# 07_-_PERIPHERALS_B.net
KiCad netlist of a schematic drawn in Altium Designer
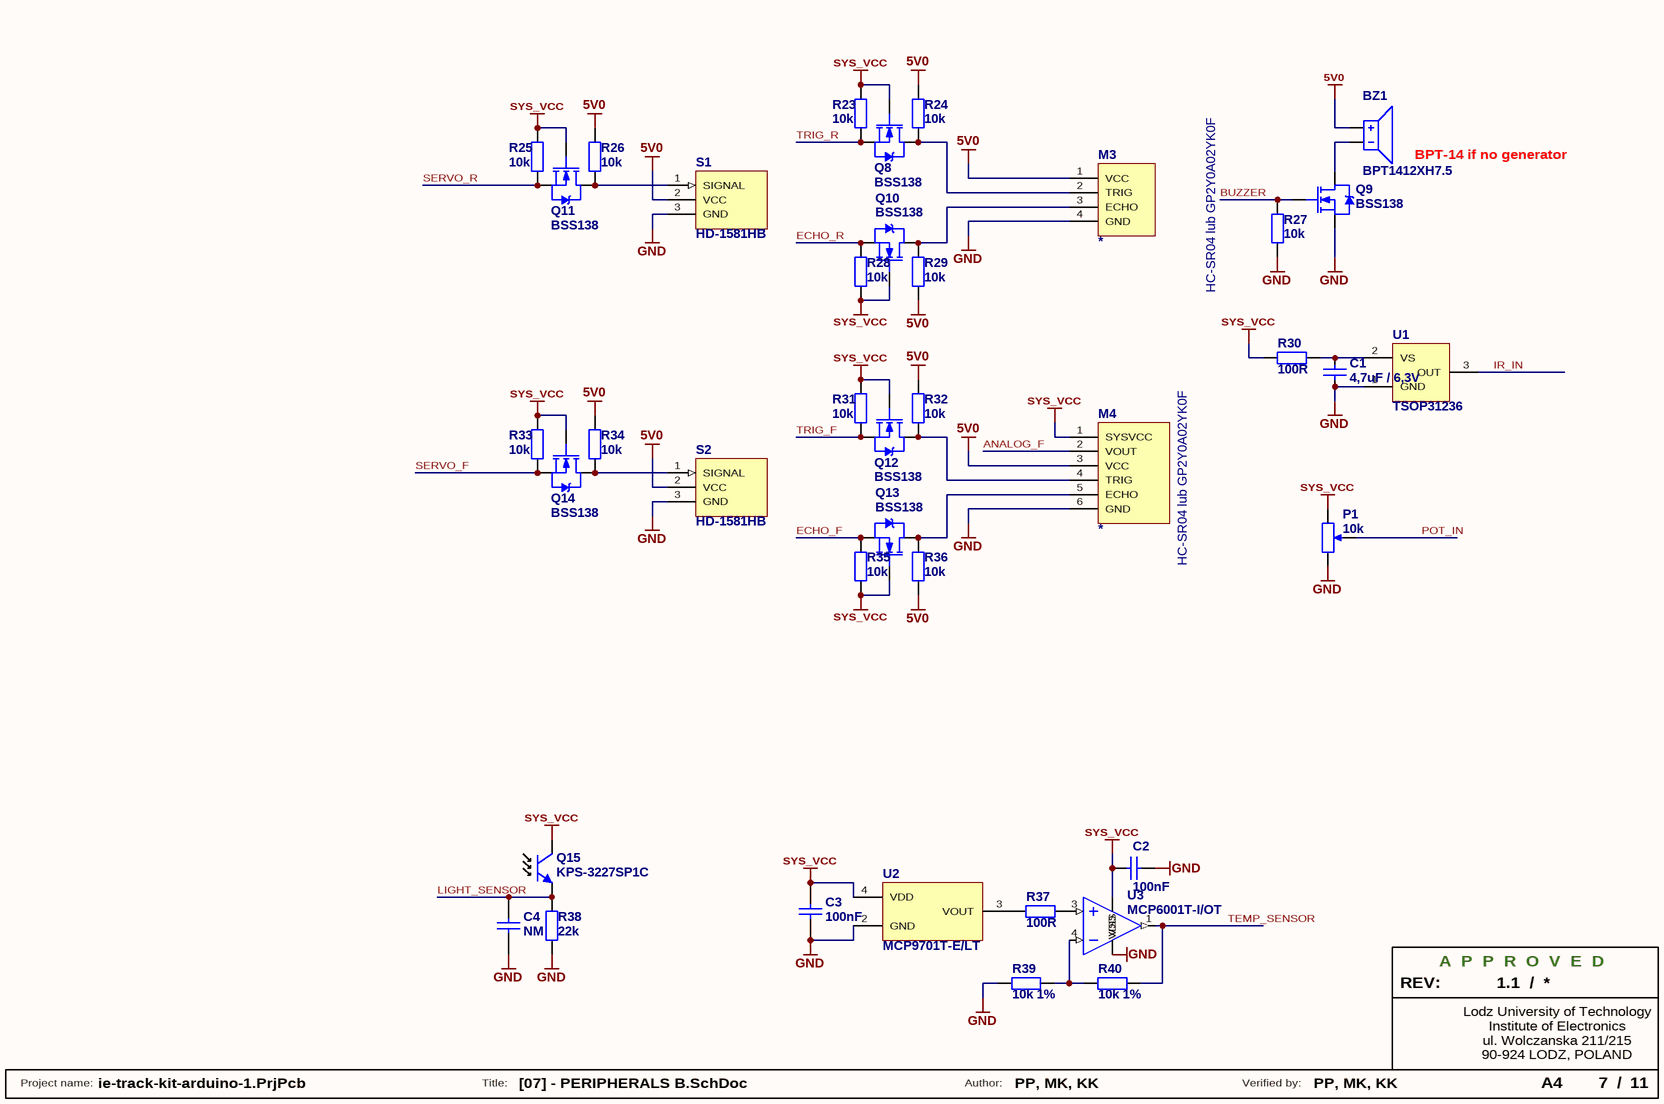
[diagram p0: [07] - PERIPHERALS B.SchDoc]

(export (version "E")
  (design (tool "Eeschema 10.0.6"))
  (components
    (comp (ref "BZ1")
      (value "BPT1412XH7.5")
      (footprint "BUZ-13,8-7,6")
      (description "Piezoelectric Sound Transducer: 5Vp-p; 4kHz; O:14mm; with generator")
      (fields (field (name "PUBLISHER") "Altium Limited"))
      (libsource (lib "sounders") (part "BPT1412XH7.5"))
    )
    (comp (ref "C1")
      (value "4,7uF / 6,3V")
      (footprint "C0805")
      (description "Capacitor")
      (libsource (lib "") (part "Cap_1"))
    )
    (comp (ref "C2")
      (value "100nF")
      (footprint "C0805")
      (description "Capacitor")
      (libsource (lib "") (part "Cap_2"))
    )
    (comp (ref "C3")
      (value "100nF")
      (footprint "C0805")
      (description "Capacitor")
      (libsource (lib "capacitors") (part "Cap"))
    )
    (comp (ref "C4")
      (value "NM")
      (footprint "C0805")
      (description "Capacitor")
      (libsource (lib "capacitors") (part "Cap"))
    )
    (comp (ref "M3") (value "*") (footprint "HC-SR04") (libsource (lib "other_modules") (part "HC-SR04")))
    (comp (ref "M4")
      (value "*")
      (footprint "HC-SR04_UNIV")
      (libsource (lib "other_modules") (part "HC-SR04_UNIVERSAL"))
    )
    (comp (ref "P1")
      (value "10k")
      (footprint "RK09K113004U")
      (description "RK09K113004U")
      (libsource (lib "resistors") (part "RK09K113004U"))
    )
    (comp (ref "Q8")
      (value "BSS138")
      (footprint "SOT-23")
      (description "N-Channel Enhancement Mode Vertical DMOS FET")
      (fields (field (name "PUBLISHER") "Altium Limited"))
      (libsource (lib "transistors_other") (part "BSS138"))
    )
    (comp (ref "Q9")
      (value "BSS138")
      (footprint "SOT-23")
      (description "N-Channel Enhancement Mode Vertical DMOS FET")
      (fields (field (name "PUBLISHER") "Altium Limited"))
      (libsource (lib "transistors_other") (part "BSS138"))
    )
    (comp (ref "Q10")
      (value "BSS138")
      (footprint "SOT-23")
      (description "N-Channel Enhancement Mode Vertical DMOS FET")
      (fields (field (name "PUBLISHER") "Altium Limited"))
      (libsource (lib "transistors_other") (part "BSS138"))
    )
    (comp (ref "Q11")
      (value "BSS138")
      (footprint "SOT-23")
      (description "N-Channel Enhancement Mode Vertical DMOS FET")
      (fields (field (name "PUBLISHER") "Altium Limited"))
      (libsource (lib "transistors_other") (part "BSS138"))
    )
    (comp (ref "Q12")
      (value "BSS138")
      (footprint "SOT-23")
      (description "N-Channel Enhancement Mode Vertical DMOS FET")
      (fields (field (name "PUBLISHER") "Altium Limited"))
      (libsource (lib "transistors_other") (part "BSS138"))
    )
    (comp (ref "Q13")
      (value "BSS138")
      (footprint "SOT-23")
      (description "N-Channel Enhancement Mode Vertical DMOS FET")
      (fields (field (name "PUBLISHER") "Altium Limited"))
      (libsource (lib "transistors_other") (part "BSS138"))
    )
    (comp (ref "Q14")
      (value "BSS138")
      (footprint "SOT-23")
      (description "N-Channel Enhancement Mode Vertical DMOS FET")
      (fields (field (name "PUBLISHER") "Altium Limited"))
      (libsource (lib "transistors_other") (part "BSS138"))
    )
    (comp (ref "Q15")
      (value "KPS-3227SP1C")
      (footprint "KPS-3227")
      (description "Photo Transistor 60V 0,1mA 580nm (TME KPS-3227SP1C)")
      (libsource (lib "photoelements") (part "KPS-3227SP1C"))
    )
    (comp (ref "R23")
      (value "10k")
      (footprint "R0805")
      (description "Resistor")
      (libsource (lib "resistors") (part "Res"))
    )
    (comp (ref "R24")
      (value "10k")
      (footprint "R0805")
      (description "Resistor")
      (libsource (lib "resistors") (part "Res"))
    )
    (comp (ref "R25")
      (value "10k")
      (footprint "R0805")
      (description "Resistor")
      (libsource (lib "resistors") (part "Res"))
    )
    (comp (ref "R26")
      (value "10k")
      (footprint "R0805")
      (description "Resistor")
      (libsource (lib "resistors") (part "Res"))
    )
    (comp (ref "R27")
      (value "10k")
      (footprint "R0805")
      (description "Resistor")
      (libsource (lib "") (part "Res_3"))
    )
    (comp (ref "R28")
      (value "10k")
      (footprint "R0805")
      (description "Resistor")
      (libsource (lib "") (part "Res_2"))
    )
    (comp (ref "R29")
      (value "10k")
      (footprint "R0805")
      (description "Resistor")
      (libsource (lib "") (part "Res_2"))
    )
    (comp (ref "R30")
      (value "100R")
      (footprint "R0805")
      (description "Resistor")
      (libsource (lib "") (part "Res_4"))
    )
    (comp (ref "R31")
      (value "10k")
      (footprint "R0805")
      (description "Resistor")
      (libsource (lib "resistors") (part "Res"))
    )
    (comp (ref "R32")
      (value "10k")
      (footprint "R0805")
      (description "Resistor")
      (libsource (lib "resistors") (part "Res"))
    )
    (comp (ref "R33")
      (value "10k")
      (footprint "R0805")
      (description "Resistor")
      (libsource (lib "resistors") (part "Res"))
    )
    (comp (ref "R34")
      (value "10k")
      (footprint "R0805")
      (description "Resistor")
      (libsource (lib "resistors") (part "Res"))
    )
    (comp (ref "R35")
      (value "10k")
      (footprint "R0805")
      (description "Resistor")
      (libsource (lib "") (part "Res_2"))
    )
    (comp (ref "R36")
      (value "10k")
      (footprint "R0805")
      (description "Resistor")
      (libsource (lib "") (part "Res_2"))
    )
    (comp (ref "R37")
      (value "100R")
      (footprint "R0805")
      (description "Resistor")
      (libsource (lib "") (part "Res_1"))
    )
    (comp (ref "R38")
      (value "22k")
      (footprint "R0805")
      (description "Resistor")
      (libsource (lib "") (part "Res_3"))
    )
    (comp (ref "R39")
      (value "10k 1%")
      (footprint "R0805")
      (description "Resistor")
      (libsource (lib "") (part "Res_1"))
    )
    (comp (ref "R40")
      (value "10k 1%")
      (footprint "R0805")
      (description "Resistor")
      (libsource (lib "") (part "Res_1"))
    )
    (comp (ref "S1")
      (value "HD-1581HB")
      (footprint "HD-1581HB_VERTICAL_1")
      (description "HD-1581HB Micro Servo")
      (libsource (lib "servos") (part "HD-1581HB"))
    )
    (comp (ref "S2")
      (value "HD-1581HB")
      (footprint "HD-1581HB_VERTICAL_1")
      (description "HD-1581HB Micro Servo")
      (libsource (lib "servos") (part "HD-1581HB"))
    )
    (comp (ref "U1")
      (value "TSOP31236")
      (footprint "TSOP312(4)_H")
      (description "36kHz IR Receiver Module for Remote Control Systems")
      (libsource (lib "ir_receivers") (part "TSOP31236"))
    )
    (comp (ref "U2")
      (value "MCP9701T-E/LT")
      (footprint "SOT-323-5 (SOT-353, SC70-5)")
      (description "Low-Power Linear Active Thermistor IC")
      (libsource (lib "temperature_transducers") (part "MCP9701T-E/LT"))
    )
    (comp (ref "U3")
      (value "MCP6001T-I/OT")
      (footprint "SOT-23-5")
      (description "Rail-to-rail, 1MHz, 100uA Op Amp")
      (libsource (lib "opamps") (part "MCP6001T-I/OT"))
    )
  )
  (nets
    (net (code "1") (name "/ANALOG_F") (class "Default")
      (node (ref "M4") (pin "2") (pinfunction "VOUT_2") (pintype "power_in"))
    )
    (net (code "2") (name "/BUZZER") (class "Default")
      (node (ref "Q9") (pin "1") (pinfunction "G_1") (pintype "passive"))
      (node (ref "R27") (pin "1") (pinfunction "1_1") (pintype "passive"))
    )
    (net (code "3") (name "/ECHO_F") (class "Default")
      (node (ref "Q13") (pin "2") (pinfunction "S_2") (pintype "passive"))
      (node (ref "R35") (pin "1") (pinfunction "1_1") (pintype "passive"))
    )
    (net (code "4") (name "/ECHO_R") (class "Default")
      (node (ref "Q10") (pin "2") (pinfunction "S_2") (pintype "passive"))
      (node (ref "R28") (pin "1") (pinfunction "1_1") (pintype "passive"))
    )
    (net (code "5") (name "/IR_IN") (class "Default")
      (node (ref "U1") (pin "3") (pinfunction "OUT_3") (pintype "passive"))
    )
    (net (code "6") (name "/LIGHT_SENSOR") (class "Default")
      (node (ref "C4") (pin "2") (pinfunction "2_2") (pintype "passive"))
      (node (ref "Q15") (pin "1") (pinfunction "E_1") (pintype "passive"))
      (node (ref "R38") (pin "1") (pinfunction "1_1") (pintype "passive"))
    )
    (net (code "7") (name "/POT_IN") (class "Default")
      (node (ref "P1") (pin "2") (pinfunction "TAP_2") (pintype "passive"))
    )
    (net (code "8") (name "/SERVO_F") (class "Default")
      (node (ref "Q14") (pin "2") (pinfunction "S_2") (pintype "passive"))
      (node (ref "R33") (pin "1") (pinfunction "1_1") (pintype "passive"))
    )
    (net (code "9") (name "/SERVO_R") (class "Default")
      (node (ref "Q11") (pin "2") (pinfunction "S_2") (pintype "passive"))
      (node (ref "R25") (pin "1") (pinfunction "1_1") (pintype "passive"))
    )
    (net (code "10") (name "/TEMP_SENSOR") (class "Default")
      (node (ref "R40") (pin "1") (pinfunction "1_1") (pintype "passive"))
      (node (ref "U3") (pin "1") (pinfunction "OUT_1") (pintype "output"))
    )
    (net (code "11") (name "/TRIG_F") (class "Default")
      (node (ref "Q12") (pin "2") (pinfunction "S_2") (pintype "passive"))
      (node (ref "R31") (pin "1") (pinfunction "1_1") (pintype "passive"))
    )
    (net (code "12") (name "/TRIG_R") (class "Default")
      (node (ref "Q8") (pin "2") (pinfunction "S_2") (pintype "passive"))
      (node (ref "R23") (pin "1") (pinfunction "1_1") (pintype "passive"))
    )
    (net (code "13") (name "5V0") (class "Default")
      (node (ref "BZ1") (pin "1") (pinfunction "1_1") (pintype "passive"))
      (node (ref "M3") (pin "1") (pinfunction "VCC_1") (pintype "power_in"))
      (node (ref "M4") (pin "3") (pinfunction "VCC_3") (pintype "power_in"))
      (node (ref "R24") (pin "2") (pinfunction "2_2") (pintype "passive"))
      (node (ref "R26") (pin "2") (pinfunction "2_2") (pintype "passive"))
      (node (ref "R29") (pin "2") (pinfunction "2_2") (pintype "passive"))
      (node (ref "R32") (pin "2") (pinfunction "2_2") (pintype "passive"))
      (node (ref "R34") (pin "2") (pinfunction "2_2") (pintype "passive"))
      (node (ref "R36") (pin "2") (pinfunction "2_2") (pintype "passive"))
      (node (ref "S1") (pin "2") (pinfunction "VCC_2") (pintype "power_in"))
      (node (ref "S2") (pin "2") (pinfunction "VCC_2") (pintype "power_in"))
    )
    (net (code "14") (name "GND") (class "Default")
      (node (ref "C1") (pin "1") (pinfunction "1_1") (pintype "passive"))
      (node (ref "C2") (pin "2") (pinfunction "2_2") (pintype "passive"))
      (node (ref "C3") (pin "1") (pinfunction "1_1") (pintype "passive"))
      (node (ref "C4") (pin "1") (pinfunction "1_1") (pintype "passive"))
      (node (ref "M3") (pin "4") (pinfunction "GND_4") (pintype "power_in"))
      (node (ref "M4") (pin "6") (pinfunction "GND_6") (pintype "power_in"))
      (node (ref "P1") (pin "3") (pinfunction "BOT_3") (pintype "passive"))
      (node (ref "Q9") (pin "2") (pinfunction "S_2") (pintype "passive"))
      (node (ref "R27") (pin "2") (pinfunction "2_2") (pintype "passive"))
      (node (ref "R38") (pin "2") (pinfunction "2_2") (pintype "passive"))
      (node (ref "R39") (pin "2") (pinfunction "2_2") (pintype "passive"))
      (node (ref "S1") (pin "3") (pinfunction "GND_3") (pintype "power_in"))
      (node (ref "S2") (pin "3") (pinfunction "GND_3") (pintype "power_in"))
      (node (ref "U1") (pin "1") (pinfunction "GND_1") (pintype "passive"))
      (node (ref "U2") (pin "2") (pinfunction "GND_2") (pintype "passive"))
      (node (ref "U3") (pin "2") (pinfunction "VSS_2") (pintype "power_in"))
    )
    (net (code "15") (name "Net-(M3-ECHO)") (class "Default")
      (node (ref "M3") (pin "3") (pinfunction "ECHO_3") (pintype "power_in"))
      (node (ref "Q10") (pin "3") (pinfunction "D_3") (pintype "passive"))
      (node (ref "R29") (pin "1") (pinfunction "1_1") (pintype "passive"))
    )
    (net (code "16") (name "Net-(M3-TRIG)") (class "Default")
      (node (ref "M3") (pin "2") (pinfunction "TRIG_2") (pintype "power_in"))
      (node (ref "Q8") (pin "3") (pinfunction "D_3") (pintype "passive"))
      (node (ref "R24") (pin "1") (pinfunction "1_1") (pintype "passive"))
    )
    (net (code "17") (name "Net-(M4-ECHO)") (class "Default")
      (node (ref "M4") (pin "5") (pinfunction "ECHO_5") (pintype "power_in"))
      (node (ref "Q13") (pin "3") (pinfunction "D_3") (pintype "passive"))
      (node (ref "R36") (pin "1") (pinfunction "1_1") (pintype "passive"))
    )
    (net (code "18") (name "Net-(M4-TRIG)") (class "Default")
      (node (ref "M4") (pin "4") (pinfunction "TRIG_4") (pintype "power_in"))
      (node (ref "Q12") (pin "3") (pinfunction "D_3") (pintype "passive"))
      (node (ref "R32") (pin "1") (pinfunction "1_1") (pintype "passive"))
    )
    (net (code "19") (name "Net-(Q9-D)") (class "Default")
      (node (ref "BZ1") (pin "2") (pinfunction "2_2") (pintype "passive"))
      (node (ref "Q9") (pin "3") (pinfunction "D_3") (pintype "passive"))
    )
    (net (code "20") (name "Net-(Q11-D)") (class "Default")
      (node (ref "Q11") (pin "3") (pinfunction "D_3") (pintype "passive"))
      (node (ref "R26") (pin "1") (pinfunction "1_1") (pintype "passive"))
      (node (ref "S1") (pin "1") (pinfunction "SIGNAL_1") (pintype "input"))
    )
    (net (code "21") (name "Net-(Q14-D)") (class "Default")
      (node (ref "Q14") (pin "3") (pinfunction "D_3") (pintype "passive"))
      (node (ref "R34") (pin "1") (pinfunction "1_1") (pintype "passive"))
      (node (ref "S2") (pin "1") (pinfunction "SIGNAL_1") (pintype "input"))
    )
    (net (code "22") (name "Net-(U1-VS)") (class "Default")
      (node (ref "C1") (pin "2") (pinfunction "2_2") (pintype "passive"))
      (node (ref "R30") (pin "2") (pinfunction "2_2") (pintype "passive"))
      (node (ref "U1") (pin "2") (pinfunction "VS_2") (pintype "passive"))
    )
    (net (code "23") (name "Net-(U2-VOUT)") (class "Default")
      (node (ref "R37") (pin "2") (pinfunction "2_2") (pintype "passive"))
      (node (ref "U2") (pin "3") (pinfunction "VOUT_3") (pintype "passive"))
    )
    (net (code "24") (name "Net-(U3-IN+)") (class "Default")
      (node (ref "R37") (pin "1") (pinfunction "1_1") (pintype "passive"))
      (node (ref "U3") (pin "3") (pinfunction "IN+_3") (pintype "input"))
    )
    (net (code "25") (name "Net-(U3-IN-)") (class "Default")
      (node (ref "R39") (pin "1") (pinfunction "1_1") (pintype "passive"))
      (node (ref "R40") (pin "2") (pinfunction "2_2") (pintype "passive"))
      (node (ref "U3") (pin "4") (pinfunction "IN-_4") (pintype "input"))
    )
    (net (code "26") (name "SYS_VCC") (class "Default")
      (node (ref "C2") (pin "1") (pinfunction "1_1") (pintype "passive"))
      (node (ref "C3") (pin "2") (pinfunction "2_2") (pintype "passive"))
      (node (ref "M4") (pin "1") (pinfunction "SYSVCC_1") (pintype "power_in"))
      (node (ref "P1") (pin "1") (pinfunction "TOP_1") (pintype "passive"))
      (node (ref "Q10") (pin "1") (pinfunction "G_1") (pintype "passive"))
      (node (ref "Q11") (pin "1") (pinfunction "G_1") (pintype "passive"))
      (node (ref "Q12") (pin "1") (pinfunction "G_1") (pintype "passive"))
      (node (ref "Q13") (pin "1") (pinfunction "G_1") (pintype "passive"))
      (node (ref "Q14") (pin "1") (pinfunction "G_1") (pintype "passive"))
      (node (ref "Q15") (pin "2") (pinfunction "C_2") (pintype "passive"))
      (node (ref "Q8") (pin "1") (pinfunction "G_1") (pintype "passive"))
      (node (ref "R23") (pin "2") (pinfunction "2_2") (pintype "passive"))
      (node (ref "R25") (pin "2") (pinfunction "2_2") (pintype "passive"))
      (node (ref "R28") (pin "2") (pinfunction "2_2") (pintype "passive"))
      (node (ref "R30") (pin "1") (pinfunction "1_1") (pintype "passive"))
      (node (ref "R31") (pin "2") (pinfunction "2_2") (pintype "passive"))
      (node (ref "R33") (pin "2") (pinfunction "2_2") (pintype "passive"))
      (node (ref "R35") (pin "2") (pinfunction "2_2") (pintype "passive"))
      (node (ref "U2") (pin "4") (pinfunction "VDD_4") (pintype "passive"))
      (node (ref "U3") (pin "5") (pinfunction "VDD_5") (pintype "power_in"))
    )
  )
)
